# Sheet.net
KiCad netlist of a schematic drawn in Altium Designer
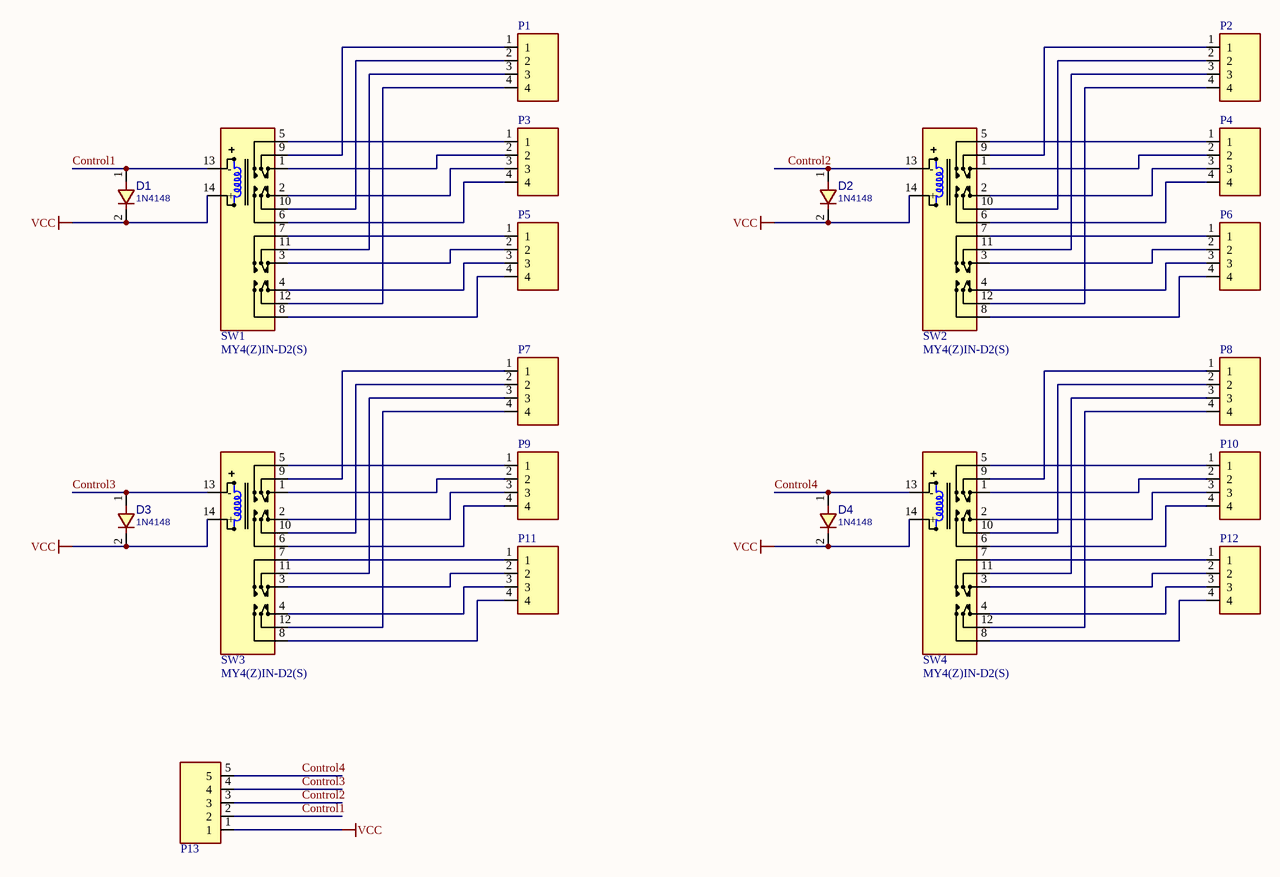
[diagram p0: Sheet.SchDoc]

(export (version "E")
  (design (tool "Eeschema 10.0.6"))
  (components
    (comp (ref "D1")
      (value "1N4148")
      (footprint "D_SOD80")
      (description "DIODE, FAST SWTICHING, 0.3A, 0.5W")
      (fields (field (name "MANF") "MANF"))
      (libsource (lib "golden_symbols") (part "DIODE_SMD_1N4148"))
    )
    (comp (ref "D2")
      (value "1N4148")
      (footprint "D_SOD80")
      (description "DIODE, FAST SWTICHING, 0.3A, 0.5W")
      (fields (field (name "MANF") "MANF"))
      (libsource (lib "golden_symbols") (part "DIODE_SMD_1N4148"))
    )
    (comp (ref "D3")
      (value "1N4148")
      (footprint "D_SOD80")
      (description "DIODE, FAST SWTICHING, 0.3A, 0.5W")
      (fields (field (name "MANF") "MANF"))
      (libsource (lib "golden_symbols") (part "DIODE_SMD_1N4148"))
    )
    (comp (ref "D4")
      (value "1N4148")
      (footprint "D_SOD80")
      (description "DIODE, FAST SWTICHING, 0.3A, 0.5W")
      (fields (field (name "MANF") "MANF"))
      (libsource (lib "golden_symbols") (part "DIODE_SMD_1N4148"))
    )
    (comp (ref "P1")
      (value "CONN_PWL_4")
      (footprint "PWL_4")
      (description "Power Terminal 4pin,Header, 4-Pin")
      (libsource (lib "Miscellaneous Connectors") (part "CONN_PWL_4"))
    )
    (comp (ref "P2")
      (value "CONN_PWL_4")
      (footprint "PWL_4")
      (description "Power Terminal 4pin,Header, 4-Pin")
      (libsource (lib "Miscellaneous Connectors") (part "CONN_PWL_4"))
    )
    (comp (ref "P3")
      (value "CONN_PWL_4")
      (footprint "PWL_4")
      (description "Power Terminal 4pin,Header, 4-Pin")
      (libsource (lib "Miscellaneous Connectors") (part "CONN_PWL_4"))
    )
    (comp (ref "P4")
      (value "CONN_PWL_4")
      (footprint "PWL_4")
      (description "Power Terminal 4pin,Header, 4-Pin")
      (libsource (lib "Miscellaneous Connectors") (part "CONN_PWL_4"))
    )
    (comp (ref "P5")
      (value "CONN_PWL_4")
      (footprint "PWL_4")
      (description "Power Terminal 4pin,Header, 4-Pin")
      (libsource (lib "Miscellaneous Connectors") (part "CONN_PWL_4"))
    )
    (comp (ref "P6")
      (value "CONN_PWL_4")
      (footprint "PWL_4")
      (description "Power Terminal 4pin,Header, 4-Pin")
      (libsource (lib "Miscellaneous Connectors") (part "CONN_PWL_4"))
    )
    (comp (ref "P7")
      (value "CONN_PWL_4")
      (footprint "PWL_4")
      (description "Power Terminal 4pin,Header, 4-Pin")
      (libsource (lib "Miscellaneous Connectors") (part "CONN_PWL_4"))
    )
    (comp (ref "P8")
      (value "CONN_PWL_4")
      (footprint "PWL_4")
      (description "Power Terminal 4pin,Header, 4-Pin")
      (libsource (lib "Miscellaneous Connectors") (part "CONN_PWL_4"))
    )
    (comp (ref "P9")
      (value "CONN_PWL_4")
      (footprint "PWL_4")
      (description "Power Terminal 4pin,Header, 4-Pin")
      (libsource (lib "Miscellaneous Connectors") (part "CONN_PWL_4"))
    )
    (comp (ref "P10")
      (value "CONN_PWL_4")
      (footprint "PWL_4")
      (description "Power Terminal 4pin,Header, 4-Pin")
      (libsource (lib "Miscellaneous Connectors") (part "CONN_PWL_4"))
    )
    (comp (ref "P11")
      (value "CONN_PWL_4")
      (footprint "PWL_4")
      (description "Power Terminal 4pin,Header, 4-Pin")
      (libsource (lib "Miscellaneous Connectors") (part "CONN_PWL_4"))
    )
    (comp (ref "P12")
      (value "CONN_PWL_4")
      (footprint "PWL_4")
      (description "Power Terminal 4pin,Header, 4-Pin")
      (libsource (lib "Miscellaneous Connectors") (part "CONN_PWL_4"))
    )
    (comp (ref "P13")
      (value "CONN_PWL_5")
      (footprint "PWL_5")
      (description "Power Terminal 5pin,Header, 5-Pin")
      (libsource (lib "Miscellaneous Connectors") (part "CONN_PWL_5"))
    )
    (comp (ref "SW1")
      (value "MY4(Z)IN-D2(S)")
      (footprint "RY-HF18FF4")
      (description "Omron 欧姆龙 功率继电器, MY4系列, 24V 直流线圈电压, 切换电流5A, 4 刀双掷, 插入 安装")
      (libsource (lib "*") (part "MY4(Z)IN-D2(S)"))
    )
    (comp (ref "SW2")
      (value "MY4(Z)IN-D2(S)")
      (footprint "RY-HF18FF4")
      (description "Omron 欧姆龙 功率继电器, MY4系列, 24V 直流线圈电压, 切换电流5A, 4 刀双掷, 插入 安装")
      (libsource (lib "*") (part "MY4(Z)IN-D2(S)"))
    )
    (comp (ref "SW3")
      (value "MY4(Z)IN-D2(S)")
      (footprint "RY-HF18FF4")
      (description "Omron 欧姆龙 功率继电器, MY4系列, 24V 直流线圈电压, 切换电流5A, 4 刀双掷, 插入 安装")
      (libsource (lib "*") (part "MY4(Z)IN-D2(S)"))
    )
    (comp (ref "SW4")
      (value "MY4(Z)IN-D2(S)")
      (footprint "RY-HF18FF4")
      (description "Omron 欧姆龙 功率继电器, MY4系列, 24V 直流线圈电压, 切换电流5A, 4 刀双掷, 插入 安装")
      (libsource (lib "*") (part "MY4(Z)IN-D2(S)"))
    )
  )
  (nets
    (net (code "1") (name "/Control1") (class "Default")
      (node (ref "D1") (pin "1") (pinfunction "1_1") (pintype "passive"))
      (node (ref "P13") (pin "2") (pinfunction "2_2") (pintype "passive"))
      (node (ref "SW1") (pin "13") (pinfunction "-_13") (pintype "passive"))
    )
    (net (code "2") (name "/Control2") (class "Default")
      (node (ref "D2") (pin "1") (pinfunction "1_1") (pintype "passive"))
      (node (ref "P13") (pin "3") (pinfunction "3_3") (pintype "passive"))
      (node (ref "SW2") (pin "13") (pinfunction "-_13") (pintype "passive"))
    )
    (net (code "3") (name "/Control3") (class "Default")
      (node (ref "D3") (pin "1") (pinfunction "1_1") (pintype "passive"))
      (node (ref "P13") (pin "4") (pinfunction "4_4") (pintype "passive"))
      (node (ref "SW3") (pin "13") (pinfunction "-_13") (pintype "passive"))
    )
    (net (code "4") (name "/Control4") (class "Default")
      (node (ref "D4") (pin "1") (pinfunction "1_1") (pintype "passive"))
      (node (ref "P13") (pin "5") (pinfunction "5_5") (pintype "passive"))
      (node (ref "SW4") (pin "13") (pinfunction "-_13") (pintype "passive"))
    )
    (net (code "5") (name "Net-(P1-Pad1)") (class "Default")
      (node (ref "P1") (pin "1") (pinfunction "1_1") (pintype "passive"))
      (node (ref "SW1") (pin "9") (pinfunction "COM1_9") (pintype "passive"))
    )
    (net (code "6") (name "Net-(P1-Pad2)") (class "Default")
      (node (ref "P1") (pin "2") (pinfunction "2_2") (pintype "passive"))
      (node (ref "SW1") (pin "10") (pinfunction "COM2_10") (pintype "passive"))
    )
    (net (code "7") (name "Net-(P1-Pad3)") (class "Default")
      (node (ref "P1") (pin "3") (pinfunction "3_3") (pintype "passive"))
      (node (ref "SW1") (pin "11") (pinfunction "COM1_11") (pintype "passive"))
    )
    (net (code "8") (name "Net-(P1-Pad4)") (class "Default")
      (node (ref "P1") (pin "4") (pinfunction "4_4") (pintype "passive"))
      (node (ref "SW1") (pin "12") (pinfunction "COM2_12") (pintype "passive"))
    )
    (net (code "9") (name "Net-(P2-Pad1)") (class "Default")
      (node (ref "P2") (pin "1") (pinfunction "1_1") (pintype "passive"))
      (node (ref "SW2") (pin "9") (pinfunction "COM1_9") (pintype "passive"))
    )
    (net (code "10") (name "Net-(P2-Pad2)") (class "Default")
      (node (ref "P2") (pin "2") (pinfunction "2_2") (pintype "passive"))
      (node (ref "SW2") (pin "10") (pinfunction "COM2_10") (pintype "passive"))
    )
    (net (code "11") (name "Net-(P2-Pad3)") (class "Default")
      (node (ref "P2") (pin "3") (pinfunction "3_3") (pintype "passive"))
      (node (ref "SW2") (pin "11") (pinfunction "COM1_11") (pintype "passive"))
    )
    (net (code "12") (name "Net-(P2-Pad4)") (class "Default")
      (node (ref "P2") (pin "4") (pinfunction "4_4") (pintype "passive"))
      (node (ref "SW2") (pin "12") (pinfunction "COM2_12") (pintype "passive"))
    )
    (net (code "13") (name "Net-(P3-Pad1)") (class "Default")
      (node (ref "P3") (pin "1") (pinfunction "1_1") (pintype "passive"))
      (node (ref "SW1") (pin "5") (pinfunction "NO1_5") (pintype "passive"))
    )
    (net (code "14") (name "Net-(P3-Pad2)") (class "Default")
      (node (ref "P3") (pin "2") (pinfunction "2_2") (pintype "passive"))
      (node (ref "SW1") (pin "1") (pinfunction "NC1_1") (pintype "passive"))
    )
    (net (code "15") (name "Net-(P3-Pad3)") (class "Default")
      (node (ref "P3") (pin "3") (pinfunction "3_3") (pintype "passive"))
      (node (ref "SW1") (pin "2") (pinfunction "NC1_2") (pintype "passive"))
    )
    (net (code "16") (name "Net-(P3-Pad4)") (class "Default")
      (node (ref "P3") (pin "4") (pinfunction "4_4") (pintype "passive"))
      (node (ref "SW1") (pin "6") (pinfunction "NO2_6") (pintype "passive"))
    )
    (net (code "17") (name "Net-(P4-Pad1)") (class "Default")
      (node (ref "P4") (pin "1") (pinfunction "1_1") (pintype "passive"))
      (node (ref "SW2") (pin "5") (pinfunction "NO1_5") (pintype "passive"))
    )
    (net (code "18") (name "Net-(P4-Pad2)") (class "Default")
      (node (ref "P4") (pin "2") (pinfunction "2_2") (pintype "passive"))
      (node (ref "SW2") (pin "1") (pinfunction "NC1_1") (pintype "passive"))
    )
    (net (code "19") (name "Net-(P4-Pad3)") (class "Default")
      (node (ref "P4") (pin "3") (pinfunction "3_3") (pintype "passive"))
      (node (ref "SW2") (pin "2") (pinfunction "NC1_2") (pintype "passive"))
    )
    (net (code "20") (name "Net-(P4-Pad4)") (class "Default")
      (node (ref "P4") (pin "4") (pinfunction "4_4") (pintype "passive"))
      (node (ref "SW2") (pin "6") (pinfunction "NO2_6") (pintype "passive"))
    )
    (net (code "21") (name "Net-(P5-Pad1)") (class "Default")
      (node (ref "P5") (pin "1") (pinfunction "1_1") (pintype "passive"))
      (node (ref "SW1") (pin "7") (pinfunction "NO1_7") (pintype "passive"))
    )
    (net (code "22") (name "Net-(P5-Pad2)") (class "Default")
      (node (ref "P5") (pin "2") (pinfunction "2_2") (pintype "passive"))
      (node (ref "SW1") (pin "3") (pinfunction "NC1_3") (pintype "passive"))
    )
    (net (code "23") (name "Net-(P5-Pad3)") (class "Default")
      (node (ref "P5") (pin "3") (pinfunction "3_3") (pintype "passive"))
      (node (ref "SW1") (pin "4") (pinfunction "NC1_4") (pintype "passive"))
    )
    (net (code "24") (name "Net-(P5-Pad4)") (class "Default")
      (node (ref "P5") (pin "4") (pinfunction "4_4") (pintype "passive"))
      (node (ref "SW1") (pin "8") (pinfunction "NO2_8") (pintype "passive"))
    )
    (net (code "25") (name "Net-(P6-Pad1)") (class "Default")
      (node (ref "P6") (pin "1") (pinfunction "1_1") (pintype "passive"))
      (node (ref "SW2") (pin "7") (pinfunction "NO1_7") (pintype "passive"))
    )
    (net (code "26") (name "Net-(P6-Pad2)") (class "Default")
      (node (ref "P6") (pin "2") (pinfunction "2_2") (pintype "passive"))
      (node (ref "SW2") (pin "3") (pinfunction "NC1_3") (pintype "passive"))
    )
    (net (code "27") (name "Net-(P6-Pad3)") (class "Default")
      (node (ref "P6") (pin "3") (pinfunction "3_3") (pintype "passive"))
      (node (ref "SW2") (pin "4") (pinfunction "NC1_4") (pintype "passive"))
    )
    (net (code "28") (name "Net-(P6-Pad4)") (class "Default")
      (node (ref "P6") (pin "4") (pinfunction "4_4") (pintype "passive"))
      (node (ref "SW2") (pin "8") (pinfunction "NO2_8") (pintype "passive"))
    )
    (net (code "29") (name "Net-(P7-Pad1)") (class "Default")
      (node (ref "P7") (pin "1") (pinfunction "1_1") (pintype "passive"))
      (node (ref "SW3") (pin "9") (pinfunction "COM1_9") (pintype "passive"))
    )
    (net (code "30") (name "Net-(P7-Pad2)") (class "Default")
      (node (ref "P7") (pin "2") (pinfunction "2_2") (pintype "passive"))
      (node (ref "SW3") (pin "10") (pinfunction "COM2_10") (pintype "passive"))
    )
    (net (code "31") (name "Net-(P7-Pad3)") (class "Default")
      (node (ref "P7") (pin "3") (pinfunction "3_3") (pintype "passive"))
      (node (ref "SW3") (pin "11") (pinfunction "COM1_11") (pintype "passive"))
    )
    (net (code "32") (name "Net-(P7-Pad4)") (class "Default")
      (node (ref "P7") (pin "4") (pinfunction "4_4") (pintype "passive"))
      (node (ref "SW3") (pin "12") (pinfunction "COM2_12") (pintype "passive"))
    )
    (net (code "33") (name "Net-(P8-Pad1)") (class "Default")
      (node (ref "P8") (pin "1") (pinfunction "1_1") (pintype "passive"))
      (node (ref "SW4") (pin "9") (pinfunction "COM1_9") (pintype "passive"))
    )
    (net (code "34") (name "Net-(P8-Pad2)") (class "Default")
      (node (ref "P8") (pin "2") (pinfunction "2_2") (pintype "passive"))
      (node (ref "SW4") (pin "10") (pinfunction "COM2_10") (pintype "passive"))
    )
    (net (code "35") (name "Net-(P8-Pad3)") (class "Default")
      (node (ref "P8") (pin "3") (pinfunction "3_3") (pintype "passive"))
      (node (ref "SW4") (pin "11") (pinfunction "COM1_11") (pintype "passive"))
    )
    (net (code "36") (name "Net-(P8-Pad4)") (class "Default")
      (node (ref "P8") (pin "4") (pinfunction "4_4") (pintype "passive"))
      (node (ref "SW4") (pin "12") (pinfunction "COM2_12") (pintype "passive"))
    )
    (net (code "37") (name "Net-(P9-Pad1)") (class "Default")
      (node (ref "P9") (pin "1") (pinfunction "1_1") (pintype "passive"))
      (node (ref "SW3") (pin "5") (pinfunction "NO1_5") (pintype "passive"))
    )
    (net (code "38") (name "Net-(P9-Pad2)") (class "Default")
      (node (ref "P9") (pin "2") (pinfunction "2_2") (pintype "passive"))
      (node (ref "SW3") (pin "1") (pinfunction "NC1_1") (pintype "passive"))
    )
    (net (code "39") (name "Net-(P9-Pad3)") (class "Default")
      (node (ref "P9") (pin "3") (pinfunction "3_3") (pintype "passive"))
      (node (ref "SW3") (pin "2") (pinfunction "NC1_2") (pintype "passive"))
    )
    (net (code "40") (name "Net-(P9-Pad4)") (class "Default")
      (node (ref "P9") (pin "4") (pinfunction "4_4") (pintype "passive"))
      (node (ref "SW3") (pin "6") (pinfunction "NO2_6") (pintype "passive"))
    )
    (net (code "41") (name "Net-(P10-Pad1)") (class "Default")
      (node (ref "P10") (pin "1") (pinfunction "1_1") (pintype "passive"))
      (node (ref "SW4") (pin "5") (pinfunction "NO1_5") (pintype "passive"))
    )
    (net (code "42") (name "Net-(P10-Pad2)") (class "Default")
      (node (ref "P10") (pin "2") (pinfunction "2_2") (pintype "passive"))
      (node (ref "SW4") (pin "1") (pinfunction "NC1_1") (pintype "passive"))
    )
    (net (code "43") (name "Net-(P10-Pad3)") (class "Default")
      (node (ref "P10") (pin "3") (pinfunction "3_3") (pintype "passive"))
      (node (ref "SW4") (pin "2") (pinfunction "NC1_2") (pintype "passive"))
    )
    (net (code "44") (name "Net-(P10-Pad4)") (class "Default")
      (node (ref "P10") (pin "4") (pinfunction "4_4") (pintype "passive"))
      (node (ref "SW4") (pin "6") (pinfunction "NO2_6") (pintype "passive"))
    )
    (net (code "45") (name "Net-(P11-Pad1)") (class "Default")
      (node (ref "P11") (pin "1") (pinfunction "1_1") (pintype "passive"))
      (node (ref "SW3") (pin "7") (pinfunction "NO1_7") (pintype "passive"))
    )
    (net (code "46") (name "Net-(P11-Pad2)") (class "Default")
      (node (ref "P11") (pin "2") (pinfunction "2_2") (pintype "passive"))
      (node (ref "SW3") (pin "3") (pinfunction "NC1_3") (pintype "passive"))
    )
    (net (code "47") (name "Net-(P11-Pad3)") (class "Default")
      (node (ref "P11") (pin "3") (pinfunction "3_3") (pintype "passive"))
      (node (ref "SW3") (pin "4") (pinfunction "NC1_4") (pintype "passive"))
    )
    (net (code "48") (name "Net-(P11-Pad4)") (class "Default")
      (node (ref "P11") (pin "4") (pinfunction "4_4") (pintype "passive"))
      (node (ref "SW3") (pin "8") (pinfunction "NO2_8") (pintype "passive"))
    )
    (net (code "49") (name "Net-(P12-Pad1)") (class "Default")
      (node (ref "P12") (pin "1") (pinfunction "1_1") (pintype "passive"))
      (node (ref "SW4") (pin "7") (pinfunction "NO1_7") (pintype "passive"))
    )
    (net (code "50") (name "Net-(P12-Pad2)") (class "Default")
      (node (ref "P12") (pin "2") (pinfunction "2_2") (pintype "passive"))
      (node (ref "SW4") (pin "3") (pinfunction "NC1_3") (pintype "passive"))
    )
    (net (code "51") (name "Net-(P12-Pad3)") (class "Default")
      (node (ref "P12") (pin "3") (pinfunction "3_3") (pintype "passive"))
      (node (ref "SW4") (pin "4") (pinfunction "NC1_4") (pintype "passive"))
    )
    (net (code "52") (name "Net-(P12-Pad4)") (class "Default")
      (node (ref "P12") (pin "4") (pinfunction "4_4") (pintype "passive"))
      (node (ref "SW4") (pin "8") (pinfunction "NO2_8") (pintype "passive"))
    )
    (net (code "53") (name "VCC") (class "Default")
      (node (ref "D1") (pin "2") (pinfunction "2_2") (pintype "passive"))
      (node (ref "D2") (pin "2") (pinfunction "2_2") (pintype "passive"))
      (node (ref "D3") (pin "2") (pinfunction "2_2") (pintype "passive"))
      (node (ref "D4") (pin "2") (pinfunction "2_2") (pintype "passive"))
      (node (ref "P13") (pin "1") (pinfunction "1_1") (pintype "passive"))
      (node (ref "SW1") (pin "14") (pinfunction "+_14") (pintype "passive"))
      (node (ref "SW2") (pin "14") (pinfunction "+_14") (pintype "passive"))
      (node (ref "SW3") (pin "14") (pinfunction "+_14") (pintype "passive"))
      (node (ref "SW4") (pin "14") (pinfunction "+_14") (pintype "passive"))
    )
  )
)
